# Accelerometer.net
KiCad netlist of a schematic drawn in Altium Designer
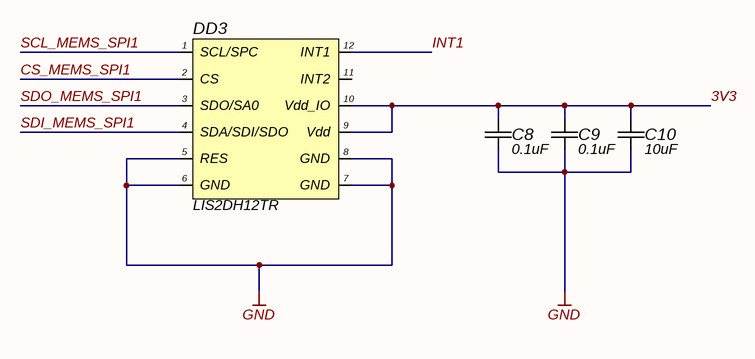
[diagram p0: Accelerometer.SchDoc]

(export (version "E")
  (design (tool "Eeschema 10.0.6"))
  (components
    (comp (ref "C8")
      (value "0.1uF")
      (footprint "CAP: 0603")
      (fields
        (field (name "MANUFACTURER") "Yageo")
        (field (name "PARTNUMBER") "CC0603KRX7R7BB104")
        (field (name "VALUEMANUFACTURERPARTNUMBER") "Ceramic capacitor, 0.1uF, X7R, ±10%, 16V, 0603, -55...+125°C")
      )
      (libsource (lib "capacitor") (part "Ceramic_0603"))
    )
    (comp (ref "C9")
      (value "0.1uF")
      (footprint "CAP: 0603")
      (fields
        (field (name "MANUFACTURER") "Yageo")
        (field (name "PARTNUMBER") "CC0603KRX7R7BB104")
        (field (name "VALUEMANUFACTURERPARTNUMBER") "Ceramic capacitor, 0.1uF, X7R, ±10%, 16V, 0603, -55...+125°C")
      )
      (libsource (lib "capacitor") (part "Ceramic_0603"))
    )
    (comp (ref "C10")
      (value "10uF")
      (footprint "CAP: 0603")
      (fields
        (field (name "MANUFACTURER") "Yageo")
        (field (name "PARTNUMBER") "CC0603KRX7R7BB104")
        (field (name "VALUEMANUFACTURERPARTNUMBER") "Ceramic capacitor, 10uF, X7R, ±10%, 16V, 0603, -55...+125°C")
      )
      (libsource (lib "capacitor") (part "Ceramic_0603"))
    )
    (comp (ref "DD3")
      (value "LIS2DH12TR")
      (footprint "12-LGA")
      (description "MEMS accelerometer")
      (libsource (lib "electromechanics") (part "LIS2DH12TR"))
    )
  )
  (nets
    (net (code "1") (name "/3V3") (class "Default")
      (node (ref "C10") (pin "2") (pinfunction "2_2") (pintype "passive"))
      (node (ref "C8") (pin "2") (pinfunction "2_2") (pintype "passive"))
      (node (ref "C9") (pin "2") (pinfunction "2_2") (pintype "passive"))
      (node (ref "DD3") (pin "10") (pinfunction "Vdd_IO_10") (pintype "passive"))
      (node (ref "DD3") (pin "9") (pinfunction "Vdd_9") (pintype "passive"))
    )
    (net (code "2") (name "/CS_MEMS_SPI1") (class "Default")
      (node (ref "DD3") (pin "2") (pinfunction "CS_2") (pintype "passive"))
    )
    (net (code "3") (name "/INT1") (class "Default")
      (node (ref "DD3") (pin "12") (pinfunction "INT1_12") (pintype "passive"))
    )
    (net (code "4") (name "/SCL_MEMS_SPI1") (class "Default")
      (node (ref "DD3") (pin "1") (pinfunction "SCL/SPC_1") (pintype "passive"))
    )
    (net (code "5") (name "/SDI_MEMS_SPI1") (class "Default")
      (node (ref "DD3") (pin "4") (pinfunction "SDA/SDI/SDO_4") (pintype "passive"))
    )
    (net (code "6") (name "/SDO_MEMS_SPI1") (class "Default")
      (node (ref "DD3") (pin "3") (pinfunction "SDO/SA0_3") (pintype "passive"))
    )
    (net (code "7") (name "GND") (class "Default")
      (node (ref "C10") (pin "1") (pinfunction "1_1") (pintype "passive"))
      (node (ref "C8") (pin "1") (pinfunction "1_1") (pintype "passive"))
      (node (ref "C9") (pin "1") (pinfunction "1_1") (pintype "passive"))
      (node (ref "DD3") (pin "5") (pinfunction "RES_5") (pintype "passive"))
      (node (ref "DD3") (pin "6") (pinfunction "GND_6") (pintype "passive"))
      (node (ref "DD3") (pin "7") (pinfunction "GND_7") (pintype "passive"))
      (node (ref "DD3") (pin "8") (pinfunction "GND_8") (pintype "passive"))
    )
    (net (code "8") (name "unconnected-(DD3-INT2-Pad11)") (class "Default")
      (node (ref "DD3") (pin "11") (pinfunction "INT2_11") (pintype "passive"))
    )
  )
)
